# HshMain_v1_0.net
KiCad netlist of a schematic drawn in EAGLE
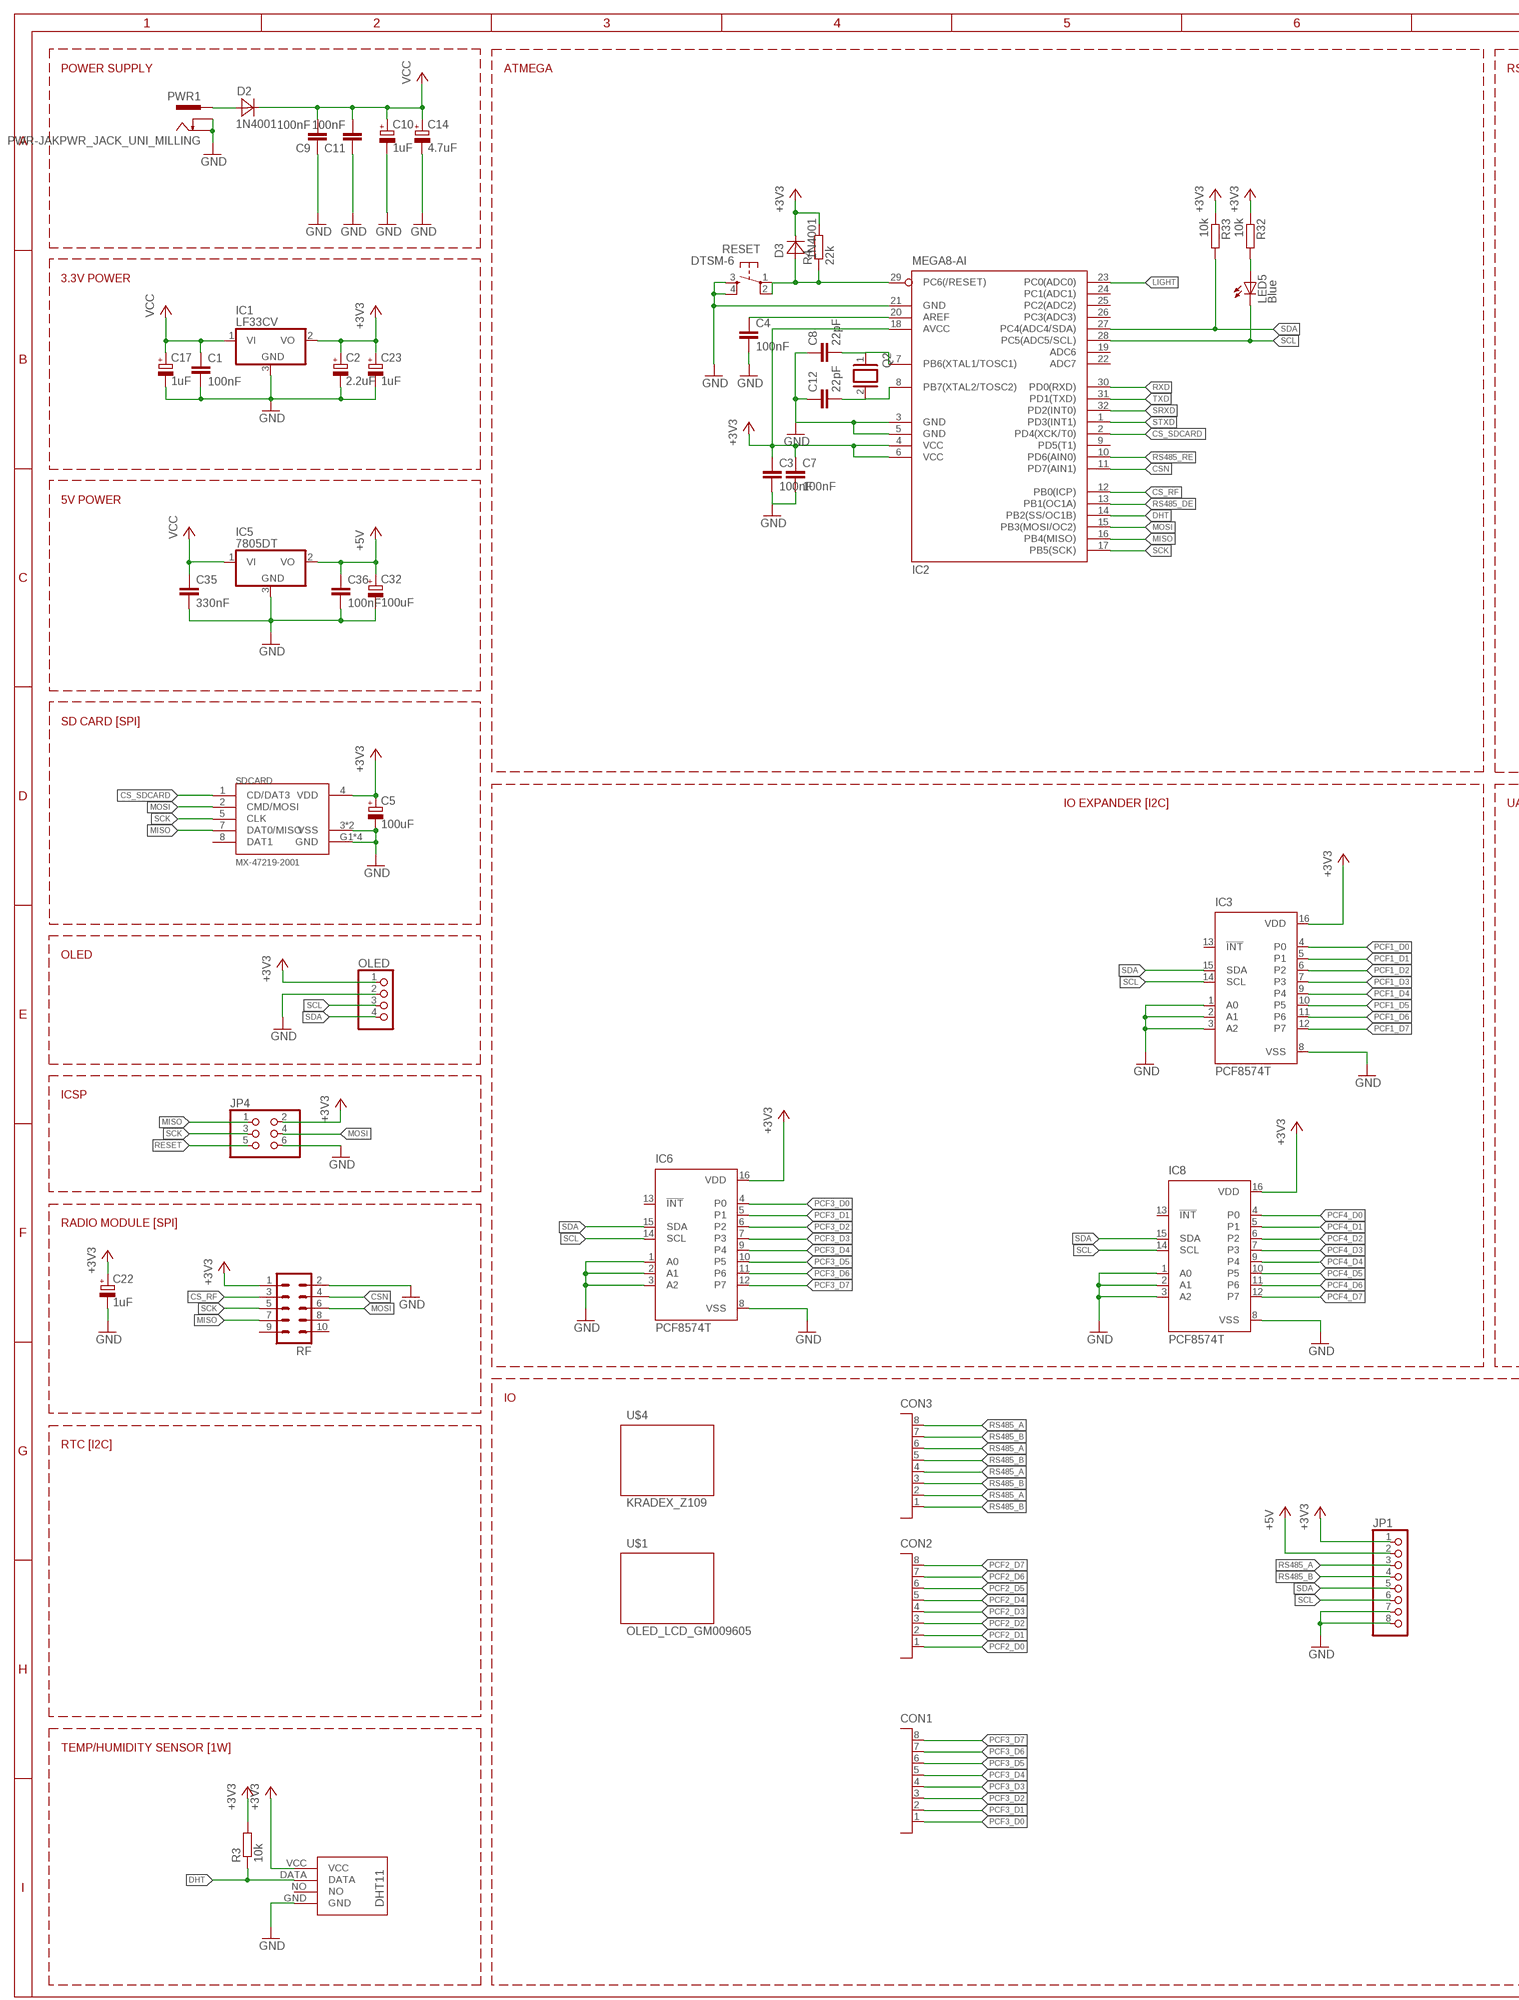
[diagram p0: schematic, sheet 1, part 1 of 2]
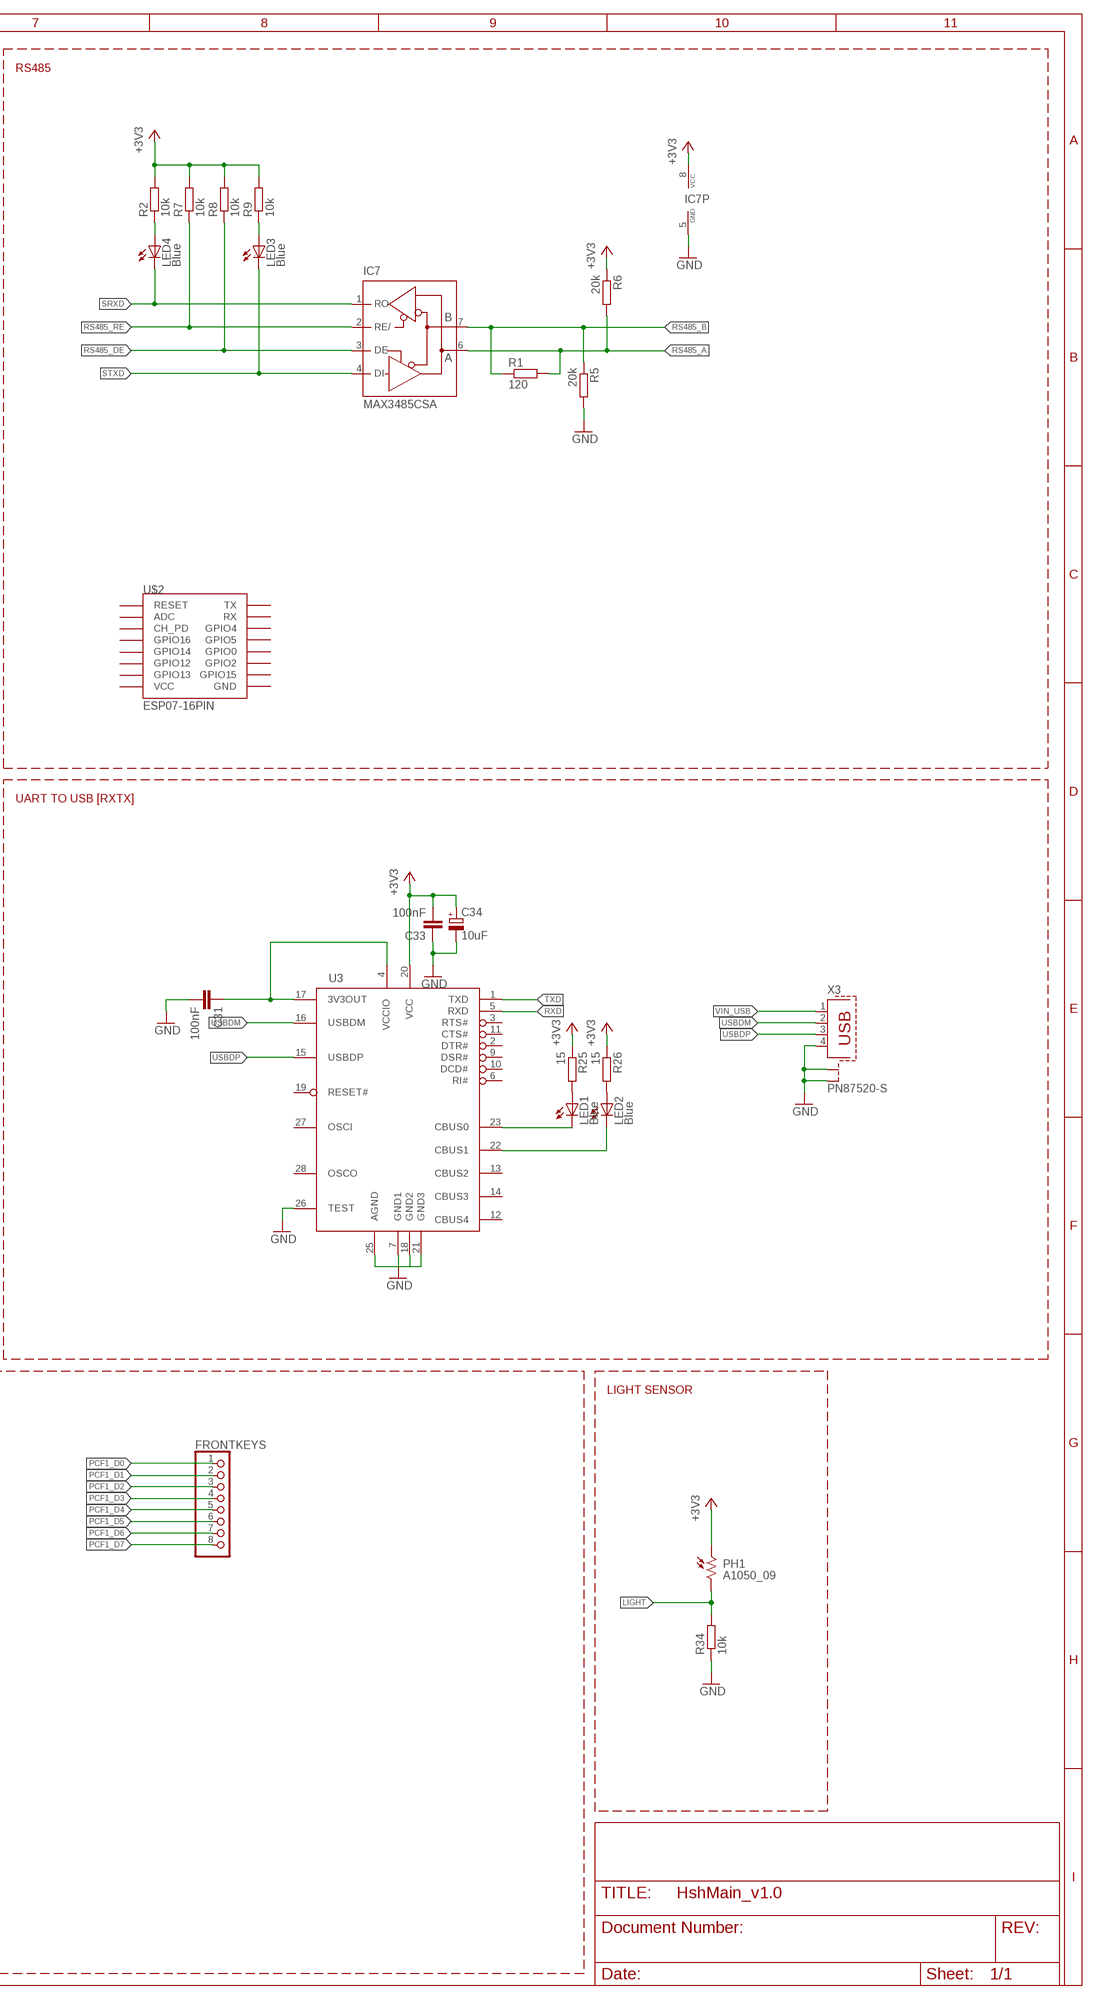
[diagram p1: schematic, sheet 1, part 2 of 2]

(export (version "E")
  (design (tool "Eeschema 10.0.6"))
  (components
    (comp (ref "C1")
      (value "100nF")
      (footprint "eagle-import:C0805")
      (libsource (lib "eagle-import") (part "C-EUC0805"))
    )
    (comp (ref "C2")
      (value "2.2uF")
      (footprint "eagle-import:PANASONIC_B")
      (libsource (lib "eagle-import") (part "CPOL-EUB"))
    )
    (comp (ref "C3")
      (value "100nF")
      (footprint "eagle-import:C0805")
      (libsource (lib "eagle-import") (part "C-EUC0805"))
    )
    (comp (ref "C4")
      (value "100nF")
      (footprint "eagle-import:C0805")
      (libsource (lib "eagle-import") (part "C-EUC0805"))
    )
    (comp (ref "C5")
      (value "100uF")
      (footprint "eagle-import:PANASONIC_D")
      (libsource (lib "eagle-import") (part "CPOL-EUD"))
    )
    (comp (ref "C7")
      (value "100nF")
      (footprint "eagle-import:C0805")
      (libsource (lib "eagle-import") (part "C-EUC0805"))
    )
    (comp (ref "C8")
      (value "22pF")
      (footprint "eagle-import:C0805")
      (libsource (lib "eagle-import") (part "C-EUC0805"))
    )
    (comp (ref "C9")
      (value "100nF")
      (footprint "eagle-import:C0805")
      (libsource (lib "eagle-import") (part "C-EUC0805"))
    )
    (comp (ref "C10")
      (value "1uF")
      (footprint "eagle-import:PANASONIC_B")
      (libsource (lib "eagle-import") (part "CPOL-EUB"))
    )
    (comp (ref "C11")
      (value "100nF")
      (footprint "eagle-import:C0805")
      (libsource (lib "eagle-import") (part "C-EUC0805"))
    )
    (comp (ref "C12")
      (value "22pF")
      (footprint "eagle-import:C0805")
      (libsource (lib "eagle-import") (part "C-EUC0805"))
    )
    (comp (ref "C14")
      (value "4.7uF")
      (footprint "eagle-import:PANASONIC_B")
      (libsource (lib "eagle-import") (part "CPOL-EUB"))
    )
    (comp (ref "C17")
      (value "1uF")
      (footprint "eagle-import:PANASONIC_B")
      (libsource (lib "eagle-import") (part "CPOL-EUB"))
    )
    (comp (ref "C22")
      (value "1uF")
      (footprint "eagle-import:PANASONIC_B")
      (libsource (lib "eagle-import") (part "CPOL-EUB"))
    )
    (comp (ref "C23")
      (value "1uF")
      (footprint "eagle-import:PANASONIC_B")
      (libsource (lib "eagle-import") (part "CPOL-EUB"))
    )
    (comp (ref "C31")
      (value "100nF")
      (footprint "eagle-import:C0805")
      (libsource (lib "eagle-import") (part "C-EUC0805"))
    )
    (comp (ref "C32")
      (value "100uF")
      (footprint "eagle-import:PANASONIC_D")
      (libsource (lib "eagle-import") (part "CPOL-EUD"))
    )
    (comp (ref "C33")
      (value "100nF")
      (footprint "eagle-import:C0805")
      (libsource (lib "eagle-import") (part "C-EUC0805"))
    )
    (comp (ref "C34")
      (value "10uF")
      (footprint "eagle-import:PANASONIC_B")
      (libsource (lib "eagle-import") (part "CPOL-EUB"))
    )
    (comp (ref "C35")
      (value "330nF")
      (footprint "eagle-import:C0805")
      (libsource (lib "eagle-import") (part "C-EUC0805"))
    )
    (comp (ref "C36")
      (value "100nF")
      (footprint "eagle-import:C0805")
      (libsource (lib "eagle-import") (part "C-EUC0805"))
    )
    (comp (ref "CON1")
      (value "15EDGRC-3.81-8P")
      (footprint "eagle-import:15EDGRC-3.81-8P")
      (libsource (lib "eagle-import") (part "15EDGRC-3.81-8P"))
    )
    (comp (ref "CON2")
      (value "15EDGRC-3.81-8P")
      (footprint "eagle-import:15EDGRC-3.81-8P")
      (libsource (lib "eagle-import") (part "15EDGRC-3.81-8P"))
    )
    (comp (ref "CON3")
      (value "15EDGRC-3.81-8P")
      (footprint "eagle-import:15EDGRC-3.81-8P")
      (libsource (lib "eagle-import") (part "15EDGRC-3.81-8P"))
    )
    (comp (ref "D2")
      (value "1N4001")
      (footprint "eagle-import:SMA")
      (libsource (lib "eagle-import") (part "MBRA340T3"))
    )
    (comp (ref "D3")
      (value "1N4001")
      (footprint "eagle-import:SMA")
      (libsource (lib "eagle-import") (part "MBRA340T3"))
    )
    (comp (ref "FRONTKEYS")
      (value "PINHD-1X8/90")
      (footprint "eagle-import:1X08_90")
      (libsource (lib "eagle-import") (part "PINHD-1X8/90"))
    )
    (comp (ref "IC1")
      (value "LF33CV")
      (footprint "eagle-import:TO252")
      (libsource (lib "eagle-import") (part "78DT"))
    )
    (comp (ref "IC2")
      (value "MEGA8-AI")
      (footprint "eagle-import:TQFP32-08")
      (fields (field (name "MPN") "ATMEGA8-16AU"))
      (libsource (lib "eagle-import") (part "MEGA8-AI"))
    )
    (comp (ref "IC3")
      (value "PCF8574T")
      (footprint "eagle-import:SO16W")
      (fields (field (name "MPN") "PCF8574T/3,512"))
      (libsource (lib "eagle-import") (part "PCF8574T"))
    )
    (comp (ref "IC5")
      (value "7805DT")
      (footprint "eagle-import:TO252")
      (libsource (lib "eagle-import") (part "linear_78DT05"))
    )
    (comp (ref "IC6")
      (value "PCF8574T")
      (footprint "eagle-import:SO16W")
      (fields (field (name "MPN") "PCF8574T/3,512"))
      (libsource (lib "eagle-import") (part "PCF8574T"))
    )
    (comp (ref "IC7")
      (value "MAX3485CSA")
      (footprint "eagle-import:SO08")
      (fields (field (name "MF") "MAXIM") (field (name "MPN") "MAX481CSA"))
      (libsource (lib "eagle-import") (part "MAX481CSA"))
    )
    (comp (ref "IC8")
      (value "PCF8574T")
      (footprint "eagle-import:SO16W")
      (fields (field (name "MPN") "PCF8574T/3,512"))
      (libsource (lib "eagle-import") (part "PCF8574T"))
    )
    (comp (ref "JP1")
      (value "PINHD-1X8/90")
      (footprint "eagle-import:1X08_90")
      (libsource (lib "eagle-import") (part "PINHD-1X8/90"))
    )
    (comp (ref "JP4")
      (value "PINHD-2X3")
      (footprint "eagle-import:2X03")
      (libsource (lib "eagle-import") (part "PINHD-2X3"))
    )
    (comp (ref "LED1")
      (value "Blue")
      (footprint "eagle-import:SML0805")
      (libsource (lib "eagle-import") (part "LEDSML0805"))
    )
    (comp (ref "LED2")
      (value "Blue")
      (footprint "eagle-import:SML0805")
      (libsource (lib "eagle-import") (part "LEDSML0805"))
    )
    (comp (ref "LED3")
      (value "Blue")
      (footprint "eagle-import:SML0805")
      (libsource (lib "eagle-import") (part "LEDSML0805"))
    )
    (comp (ref "LED4")
      (value "Blue")
      (footprint "eagle-import:SML0805")
      (libsource (lib "eagle-import") (part "LEDSML0805"))
    )
    (comp (ref "LED5")
      (value "Blue")
      (footprint "eagle-import:SML0805")
      (libsource (lib "eagle-import") (part "LEDSML0805"))
    )
    (comp (ref "OLED")
      (value "PINHD-1X4")
      (footprint "eagle-import:1X04")
      (libsource (lib "eagle-import") (part "PINHD-1X4"))
    )
    (comp (ref "PH1")
      (value "A1050_09")
      (footprint "eagle-import:T0-46-A10XX")
      (libsource (lib "eagle-import") (part "A1050_09"))
    )
    (comp (ref "PWR1")
      (value "PWR-JAKPWR_JACK_UNI_MILLING")
      (footprint "eagle-import:PWR_JACK_UNI_MILLING")
      (libsource (lib "eagle-import") (part "PWR-JAKPWR_JACK_UNI_MILLING"))
    )
    (comp (ref "Q2")
      (value "XTAL/S")
      (footprint "eagle-import:QS")
      (libsource (lib "eagle-import") (part "XTAL/S"))
    )
    (comp (ref "R1")
      (value "120")
      (footprint "eagle-import:R0805")
      (libsource (lib "eagle-import") (part "R-EU_R0805"))
    )
    (comp (ref "R2")
      (value "10k")
      (footprint "eagle-import:R0805")
      (libsource (lib "eagle-import") (part "R-EU_R0805"))
    )
    (comp (ref "R3")
      (value "10k")
      (footprint "eagle-import:R0805")
      (libsource (lib "eagle-import") (part "R-EU_R0805"))
    )
    (comp (ref "R4")
      (value "22k")
      (footprint "eagle-import:R0805")
      (libsource (lib "eagle-import") (part "R-EU_R0805"))
    )
    (comp (ref "R5")
      (value "20k")
      (footprint "eagle-import:R0805")
      (libsource (lib "eagle-import") (part "R-EU_R0805"))
    )
    (comp (ref "R6")
      (value "20k")
      (footprint "eagle-import:R0805")
      (libsource (lib "eagle-import") (part "R-EU_R0805"))
    )
    (comp (ref "R7")
      (value "10k")
      (footprint "eagle-import:R0805")
      (libsource (lib "eagle-import") (part "R-EU_R0805"))
    )
    (comp (ref "R8")
      (value "10k")
      (footprint "eagle-import:R0805")
      (libsource (lib "eagle-import") (part "R-EU_R0805"))
    )
    (comp (ref "R9")
      (value "10k")
      (footprint "eagle-import:R0805")
      (libsource (lib "eagle-import") (part "R-EU_R0805"))
    )
    (comp (ref "R25")
      (value "15")
      (footprint "eagle-import:R0805")
      (libsource (lib "eagle-import") (part "R-EU_R0805"))
    )
    (comp (ref "R26")
      (value "15")
      (footprint "eagle-import:R0805")
      (libsource (lib "eagle-import") (part "R-EU_R0805"))
    )
    (comp (ref "R32")
      (value "10k")
      (footprint "eagle-import:R0805")
      (libsource (lib "eagle-import") (part "R-EU_R0805"))
    )
    (comp (ref "R33")
      (value "10k")
      (footprint "eagle-import:R0805")
      (libsource (lib "eagle-import") (part "R-EU_R0805"))
    )
    (comp (ref "R34")
      (value "10k")
      (footprint "eagle-import:R0805")
      (libsource (lib "eagle-import") (part "R-EU_R0805"))
    )
    (comp (ref "RESET")
      (value "DTSM-6")
      (footprint "eagle-import:DTSM-6")
      (libsource (lib "eagle-import") (part "DTSM-6"))
    )
    (comp (ref "RF")
      (value "ML10")
      (footprint "eagle-import:ML10")
      (libsource (lib "eagle-import") (part "ML10"))
    )
    (comp (ref "SDCARD")
      (value "MX-47219-2001")
      (footprint "eagle-import:MX-47219-2001")
      (libsource (lib "eagle-import") (part "MX-47219-2001"))
    )
    (comp (ref "U$1")
      (value "OLED_LCD_GM009605")
      (footprint "eagle-import:OLED_LCD_GM009605")
      (libsource (lib "eagle-import") (part "OLED_LCD_GM009605"))
    )
    (comp (ref "U$2")
      (value "ESP07-16PIN")
      (footprint "eagle-import:ESP07-16PIN")
      (libsource (lib "eagle-import") (part "ESP07-16PIN"))
    )
    (comp (ref "U$3")
      (value "DHT11-PION.")
      (footprint "eagle-import:DHT11-PION.")
      (libsource (lib "eagle-import") (part "DHT11-PION."))
    )
    (comp (ref "U$4")
      (value "KRADEX_Z109")
      (footprint "eagle-import:KRADEX_Z109")
      (libsource (lib "eagle-import") (part "KRADEX_Z109"))
    )
    (comp (ref "U3")
      (value "FT232RL")
      (footprint "eagle-import:SSOP28DB")
      (libsource (lib "eagle-import") (part "FT232RL"))
    )
    (comp (ref "X3")
      (value "PN87520-S")
      (footprint "eagle-import:PN87520-S")
      (libsource (lib "eagle-import") (part "PN87520-S"))
    )
  )
  (nets
    (net (code "1") (name "+3V3") (class "Default")
      (node (ref "C2") (pin "+") (pinfunction "+_+") (pintype "passive"))
      (node (ref "C22") (pin "+") (pinfunction "+_+") (pintype "passive"))
      (node (ref "C23") (pin "+") (pinfunction "+_+") (pintype "passive"))
      (node (ref "C3") (pin "1") (pinfunction "1_1") (pintype "passive"))
      (node (ref "C33") (pin "2") (pinfunction "2_2") (pintype "passive"))
      (node (ref "C34") (pin "+") (pinfunction "+_+") (pintype "passive"))
      (node (ref "C5") (pin "+") (pinfunction "+_+") (pintype "passive"))
      (node (ref "C7") (pin "1") (pinfunction "1_1") (pintype "passive"))
      (node (ref "D3") (pin "C") (pinfunction "C_C") (pintype "passive"))
      (node (ref "IC1") (pin "2") (pinfunction "VO_2") (pintype "passive"))
      (node (ref "IC2") (pin "18") (pinfunction "AVCC_18") (pintype "power_in"))
      (node (ref "IC2") (pin "4") (pinfunction "VCC_4") (pintype "power_in"))
      (node (ref "IC2") (pin "6") (pinfunction "VCC_6") (pintype "power_in"))
      (node (ref "IC3") (pin "16") (pinfunction "VDD_16") (pintype "power_in"))
      (node (ref "IC6") (pin "16") (pinfunction "VDD_16") (pintype "power_in"))
      (node (ref "IC7") (pin "8") (pinfunction "VCC_8") (pintype "power_in"))
      (node (ref "IC8") (pin "16") (pinfunction "VDD_16") (pintype "power_in"))
      (node (ref "JP1") (pin "1") (pinfunction "1_1") (pintype "passive"))
      (node (ref "JP4") (pin "2") (pinfunction "2_2") (pintype "passive"))
      (node (ref "OLED") (pin "1") (pinfunction "1_1") (pintype "passive"))
      (node (ref "PH1") (pin "1") (pinfunction "1_1") (pintype "passive"))
      (node (ref "R2") (pin "2") (pinfunction "2_2") (pintype "passive"))
      (node (ref "R25") (pin "1") (pinfunction "1_1") (pintype "passive"))
      (node (ref "R26") (pin "1") (pinfunction "1_1") (pintype "passive"))
      (node (ref "R3") (pin "2") (pinfunction "2_2") (pintype "passive"))
      (node (ref "R32") (pin "1") (pinfunction "1_1") (pintype "passive"))
      (node (ref "R33") (pin "1") (pinfunction "1_1") (pintype "passive"))
      (node (ref "R4") (pin "2") (pinfunction "2_2") (pintype "passive"))
      (node (ref "R6") (pin "1") (pinfunction "1_1") (pintype "passive"))
      (node (ref "R7") (pin "2") (pinfunction "2_2") (pintype "passive"))
      (node (ref "R8") (pin "2") (pinfunction "2_2") (pintype "passive"))
      (node (ref "R9") (pin "2") (pinfunction "2_2") (pintype "passive"))
      (node (ref "RF") (pin "1") (pinfunction "1_1") (pintype "passive"))
      (node (ref "SDCARD") (pin "4") (pinfunction "VDD_4") (pintype "bidirectional"))
      (node (ref "U$3") (pin "VCC") (pinfunction "VCC_VCC") (pintype "bidirectional"))
      (node (ref "U3") (pin "20") (pinfunction "VCC_20") (pintype "power_in"))
    )
    (net (code "2") (name "+5V") (class "Default")
      (node (ref "C32") (pin "+") (pinfunction "+_+") (pintype "passive"))
      (node (ref "C36") (pin "1") (pinfunction "1_1") (pintype "passive"))
      (node (ref "IC5") (pin "2") (pinfunction "VO_2") (pintype "passive"))
      (node (ref "JP1") (pin "2") (pinfunction "2_2") (pintype "passive"))
    )
    (net (code "3") (name "CSN") (class "Default")
      (node (ref "IC2") (pin "11") (pinfunction "PD7(AIN1)_11") (pintype "bidirectional"))
      (node (ref "RF") (pin "4") (pinfunction "4_4") (pintype "passive"))
    )
    (net (code "4") (name "CS_RF") (class "Default")
      (node (ref "IC2") (pin "12") (pinfunction "PB0(ICP)_12") (pintype "bidirectional"))
      (node (ref "RF") (pin "3") (pinfunction "3_3") (pintype "passive"))
    )
    (net (code "5") (name "CS_SDCARD") (class "Default")
      (node (ref "IC2") (pin "2") (pinfunction "PD4(XCK/T0)_2") (pintype "bidirectional"))
      (node (ref "SDCARD") (pin "1") (pinfunction "CD/DAT3_1") (pintype "bidirectional"))
    )
    (net (code "6") (name "DHT") (class "Default")
      (node (ref "IC2") (pin "14") (pinfunction "PB2(SS/OC1B)_14") (pintype "bidirectional"))
      (node (ref "R3") (pin "1") (pinfunction "1_1") (pintype "passive"))
      (node (ref "U$3") (pin "DATA") (pinfunction "DATA_DATA") (pintype "bidirectional"))
    )
    (net (code "7") (name "GND") (class "Default")
      (node (ref "C1") (pin "2") (pinfunction "2_2") (pintype "passive"))
      (node (ref "C10") (pin "-") (pinfunction "-_-") (pintype "passive"))
      (node (ref "C11") (pin "1") (pinfunction "1_1") (pintype "passive"))
      (node (ref "C12") (pin "1") (pinfunction "1_1") (pintype "passive"))
      (node (ref "C14") (pin "-") (pinfunction "-_-") (pintype "passive"))
      (node (ref "C17") (pin "-") (pinfunction "-_-") (pintype "passive"))
      (node (ref "C2") (pin "-") (pinfunction "-_-") (pintype "passive"))
      (node (ref "C22") (pin "-") (pinfunction "-_-") (pintype "passive"))
      (node (ref "C23") (pin "-") (pinfunction "-_-") (pintype "passive"))
      (node (ref "C3") (pin "2") (pinfunction "2_2") (pintype "passive"))
      (node (ref "C31") (pin "2") (pinfunction "2_2") (pintype "passive"))
      (node (ref "C32") (pin "-") (pinfunction "-_-") (pintype "passive"))
      (node (ref "C33") (pin "1") (pinfunction "1_1") (pintype "passive"))
      (node (ref "C34") (pin "-") (pinfunction "-_-") (pintype "passive"))
      (node (ref "C35") (pin "2") (pinfunction "2_2") (pintype "passive"))
      (node (ref "C36") (pin "2") (pinfunction "2_2") (pintype "passive"))
      (node (ref "C4") (pin "2") (pinfunction "2_2") (pintype "passive"))
      (node (ref "C5") (pin "-") (pinfunction "-_-") (pintype "passive"))
      (node (ref "C7") (pin "2") (pinfunction "2_2") (pintype "passive"))
      (node (ref "C8") (pin "1") (pinfunction "1_1") (pintype "passive"))
      (node (ref "C9") (pin "1") (pinfunction "1_1") (pintype "passive"))
      (node (ref "IC1") (pin "3") (pinfunction "GND_3") (pintype "passive"))
      (node (ref "IC2") (pin "21") (pinfunction "GND_21") (pintype "power_in"))
      (node (ref "IC2") (pin "3") (pinfunction "GND_3") (pintype "power_in"))
      (node (ref "IC2") (pin "5") (pinfunction "GND_5") (pintype "power_in"))
      (node (ref "IC3") (pin "1") (pinfunction "A0_1") (pintype "input"))
      (node (ref "IC3") (pin "2") (pinfunction "A1_2") (pintype "input"))
      (node (ref "IC3") (pin "3") (pinfunction "A2_3") (pintype "input"))
      (node (ref "IC3") (pin "8") (pinfunction "VSS_8") (pintype "power_in"))
      (node (ref "IC5") (pin "3") (pinfunction "GND_3") (pintype "passive"))
      (node (ref "IC6") (pin "1") (pinfunction "A0_1") (pintype "input"))
      (node (ref "IC6") (pin "2") (pinfunction "A1_2") (pintype "input"))
      (node (ref "IC6") (pin "3") (pinfunction "A2_3") (pintype "input"))
      (node (ref "IC6") (pin "8") (pinfunction "VSS_8") (pintype "power_in"))
      (node (ref "IC7") (pin "5") (pinfunction "GND_5") (pintype "power_in"))
      (node (ref "IC8") (pin "1") (pinfunction "A0_1") (pintype "input"))
      (node (ref "IC8") (pin "2") (pinfunction "A1_2") (pintype "input"))
      (node (ref "IC8") (pin "3") (pinfunction "A2_3") (pintype "input"))
      (node (ref "IC8") (pin "8") (pinfunction "VSS_8") (pintype "power_in"))
      (node (ref "JP1") (pin "7") (pinfunction "7_7") (pintype "passive"))
      (node (ref "JP1") (pin "8") (pinfunction "8_8") (pintype "passive"))
      (node (ref "JP4") (pin "6") (pinfunction "6_6") (pintype "passive"))
      (node (ref "OLED") (pin "2") (pinfunction "2_2") (pintype "passive"))
      (node (ref "PWR1") (pin "-") (pinfunction "-_-") (pintype "passive"))
      (node (ref "PWR1") (pin "--") (pinfunction "--_--") (pintype "passive"))
      (node (ref "PWR1") (pin "--1") (pinfunction "--_--1") (pintype "passive"))
      (node (ref "PWR1") (pin "--2") (pinfunction "--_--2") (pintype "passive"))
      (node (ref "PWR1") (pin "--3") (pinfunction "--_--3") (pintype "passive"))
      (node (ref "PWR1") (pin "--4") (pinfunction "--_--4") (pintype "passive"))
      (node (ref "PWR1") (pin "--5") (pinfunction "--_--5") (pintype "passive"))
      (node (ref "PWR1") (pin "--6") (pinfunction "--_--6") (pintype "passive"))
      (node (ref "PWR1") (pin "--7") (pinfunction "--_--7") (pintype "passive"))
      (node (ref "PWR1") (pin "--8") (pinfunction "--_--8") (pintype "passive"))
      (node (ref "PWR1") (pin "-1") (pinfunction "-_-1") (pintype "passive"))
      (node (ref "PWR1") (pin "-2") (pinfunction "-_-2") (pintype "passive"))
      (node (ref "PWR1") (pin "-3") (pinfunction "-_-3") (pintype "passive"))
      (node (ref "PWR1") (pin "-4") (pinfunction "-_-4") (pintype "passive"))
      (node (ref "PWR1") (pin "-5") (pinfunction "-_-5") (pintype "passive"))
      (node (ref "PWR1") (pin "-6") (pinfunction "-_-6") (pintype "passive"))
      (node (ref "PWR1") (pin "-7") (pinfunction "-_-7") (pintype "passive"))
      (node (ref "PWR1") (pin "-8") (pinfunction "-_-8") (pintype "passive"))
      (node (ref "R34") (pin "1") (pinfunction "1_1") (pintype "passive"))
      (node (ref "R5") (pin "2") (pinfunction "2_2") (pintype "passive"))
      (node (ref "RESET") (pin "3") (pinfunction "3_3") (pintype "passive"))
      (node (ref "RESET") (pin "4") (pinfunction "4_4") (pintype "passive"))
      (node (ref "RF") (pin "2") (pinfunction "2_2") (pintype "passive"))
      (node (ref "SDCARD") (pin "3") (pinfunction "VSS_3") (pintype "bidirectional"))
      (node (ref "SDCARD") (pin "6") (pinfunction "VSS_6") (pintype "bidirectional"))
      (node (ref "SDCARD") (pin "G1") (pinfunction "GND_G1") (pintype "bidirectional"))
      (node (ref "SDCARD") (pin "G2") (pinfunction "GND_G2") (pintype "bidirectional"))
      (node (ref "SDCARD") (pin "G3") (pinfunction "GND_G3") (pintype "bidirectional"))
      (node (ref "SDCARD") (pin "G4") (pinfunction "GND_G4") (pintype "bidirectional"))
      (node (ref "U$3") (pin "GND") (pinfunction "GND_GND") (pintype "bidirectional"))
      (node (ref "U3") (pin "18") (pinfunction "GND2_18") (pintype "power_in"))
      (node (ref "U3") (pin "21") (pinfunction "GND3_21") (pintype "power_in"))
      (node (ref "U3") (pin "25") (pinfunction "AGND_25") (pintype "power_in"))
      (node (ref "U3") (pin "26") (pinfunction "TEST_26") (pintype "input"))
      (node (ref "U3") (pin "7") (pinfunction "GND1_7") (pintype "power_in"))
      (node (ref "X3") (pin "4") (pinfunction "4_4") (pintype "passive"))
      (node (ref "X3") (pin "S1") (pinfunction "S1_S1") (pintype "passive"))
      (node (ref "X3") (pin "S2") (pinfunction "S2_S2") (pintype "passive"))
    )
    (net (code "8") (name "LIGHT") (class "Default")
      (node (ref "IC2") (pin "23") (pinfunction "PC0(ADC0)_23") (pintype "bidirectional"))
      (node (ref "PH1") (pin "2") (pinfunction "2_2") (pintype "passive"))
      (node (ref "R34") (pin "2") (pinfunction "2_2") (pintype "passive"))
    )
    (net (code "9") (name "MISO") (class "Default")
      (node (ref "IC2") (pin "16") (pinfunction "PB4(MISO)_16") (pintype "bidirectional"))
      (node (ref "JP4") (pin "1") (pinfunction "1_1") (pintype "passive"))
      (node (ref "RF") (pin "7") (pinfunction "7_7") (pintype "passive"))
      (node (ref "SDCARD") (pin "7") (pinfunction "DAT0/MISO_7") (pintype "bidirectional"))
    )
    (net (code "10") (name "MOSI") (class "Default")
      (node (ref "IC2") (pin "15") (pinfunction "PB3(MOSI/OC2)_15") (pintype "bidirectional"))
      (node (ref "JP4") (pin "4") (pinfunction "4_4") (pintype "passive"))
      (node (ref "RF") (pin "6") (pinfunction "6_6") (pintype "passive"))
      (node (ref "SDCARD") (pin "2") (pinfunction "CMD/MOSI_2") (pintype "bidirectional"))
    )
    (net (code "11") (name "Net-(D2-PadA)") (class "Default")
      (node (ref "D2") (pin "A") (pinfunction "A_A") (pintype "passive"))
      (node (ref "PWR1") (pin "+") (pinfunction "+_+") (pintype "passive"))
      (node (ref "PWR1") (pin "+1") (pinfunction "+_+1") (pintype "passive"))
      (node (ref "PWR1") (pin "+2") (pinfunction "+_+2") (pintype "passive"))
      (node (ref "PWR1") (pin "+3") (pinfunction "+_+3") (pintype "passive"))
      (node (ref "PWR1") (pin "+4") (pinfunction "+_+4") (pintype "passive"))
      (node (ref "PWR1") (pin "+5") (pinfunction "+_+5") (pintype "passive"))
      (node (ref "PWR1") (pin "+6") (pinfunction "+_+6") (pintype "passive"))
      (node (ref "PWR1") (pin "+7") (pinfunction "+_+7") (pintype "passive"))
      (node (ref "PWR1") (pin "+8") (pinfunction "+_+8") (pintype "passive"))
    )
    (net (code "12") (name "Net-(IC2-AREF)") (class "Default")
      (node (ref "C4") (pin "1") (pinfunction "1_1") (pintype "passive"))
      (node (ref "IC2") (pin "20") (pinfunction "AREF_20") (pintype "passive"))
    )
    (net (code "13") (name "Net-(IC2-PB6(XTAL1{slash}TOSC1))") (class "Default")
      (node (ref "C8") (pin "2") (pinfunction "2_2") (pintype "passive"))
      (node (ref "IC2") (pin "7") (pinfunction "PB6(XTAL1/TOSC1)_7") (pintype "bidirectional"))
      (node (ref "Q2") (pin "1") (pinfunction "1_1") (pintype "passive"))
    )
    (net (code "14") (name "Net-(IC2-PB7(XTAL2{slash}TOSC2))") (class "Default")
      (node (ref "C12") (pin "2") (pinfunction "2_2") (pintype "passive"))
      (node (ref "IC2") (pin "8") (pinfunction "PB7(XTAL2/TOSC2)_8") (pintype "bidirectional"))
      (node (ref "Q2") (pin "2") (pinfunction "2_2") (pintype "passive"))
    )
    (net (code "15") (name "Net-(LED1-PadA)") (class "Default")
      (node (ref "LED1") (pin "A") (pinfunction "A_A") (pintype "passive"))
      (node (ref "R25") (pin "2") (pinfunction "2_2") (pintype "passive"))
    )
    (net (code "16") (name "Net-(LED2-PadA)") (class "Default")
      (node (ref "LED2") (pin "A") (pinfunction "A_A") (pintype "passive"))
      (node (ref "R26") (pin "2") (pinfunction "2_2") (pintype "passive"))
    )
    (net (code "17") (name "Net-(LED3-PadA)") (class "Default")
      (node (ref "LED3") (pin "A") (pinfunction "A_A") (pintype "passive"))
      (node (ref "R9") (pin "1") (pinfunction "1_1") (pintype "passive"))
    )
    (net (code "18") (name "Net-(LED4-PadA)") (class "Default")
      (node (ref "LED4") (pin "A") (pinfunction "A_A") (pintype "passive"))
      (node (ref "R2") (pin "1") (pinfunction "1_1") (pintype "passive"))
    )
    (net (code "19") (name "Net-(LED5-PadA)") (class "Default")
      (node (ref "LED5") (pin "A") (pinfunction "A_A") (pintype "passive"))
      (node (ref "R32") (pin "2") (pinfunction "2_2") (pintype "passive"))
    )
    (net (code "20") (name "Net-(U3-3V3OUT)") (class "Default")
      (node (ref "C31") (pin "1") (pinfunction "1_1") (pintype "passive"))
      (node (ref "U3") (pin "17") (pinfunction "3V3OUT_17") (pintype "output"))
      (node (ref "U3") (pin "4") (pinfunction "VCCIO_4") (pintype "power_in"))
    )
    (net (code "21") (name "Net-(U3-CBUS0)") (class "Default")
      (node (ref "LED1") (pin "C") (pinfunction "C_C") (pintype "passive"))
      (node (ref "U3") (pin "23") (pinfunction "CBUS0_23") (pintype "bidirectional"))
    )
    (net (code "22") (name "Net-(U3-CBUS1)") (class "Default")
      (node (ref "LED2") (pin "C") (pinfunction "C_C") (pintype "passive"))
      (node (ref "U3") (pin "22") (pinfunction "CBUS1_22") (pintype "bidirectional"))
    )
    (net (code "23") (name "PCF1_D0") (class "Default")
      (node (ref "FRONTKEYS") (pin "1") (pinfunction "1_1") (pintype "passive"))
      (node (ref "IC3") (pin "4") (pinfunction "P0_4") (pintype "bidirectional"))
    )
    (net (code "24") (name "PCF1_D1") (class "Default")
      (node (ref "FRONTKEYS") (pin "2") (pinfunction "2_2") (pintype "passive"))
      (node (ref "IC3") (pin "5") (pinfunction "P1_5") (pintype "bidirectional"))
    )
    (net (code "25") (name "PCF1_D2") (class "Default")
      (node (ref "FRONTKEYS") (pin "3") (pinfunction "3_3") (pintype "passive"))
      (node (ref "IC3") (pin "6") (pinfunction "P2_6") (pintype "bidirectional"))
    )
    (net (code "26") (name "PCF1_D3") (class "Default")
      (node (ref "FRONTKEYS") (pin "4") (pinfunction "4_4") (pintype "passive"))
      (node (ref "IC3") (pin "7") (pinfunction "P3_7") (pintype "bidirectional"))
    )
    (net (code "27") (name "PCF1_D4") (class "Default")
      (node (ref "FRONTKEYS") (pin "5") (pinfunction "5_5") (pintype "passive"))
      (node (ref "IC3") (pin "9") (pinfunction "P4_9") (pintype "bidirectional"))
    )
    (net (code "28") (name "PCF1_D5") (class "Default")
      (node (ref "FRONTKEYS") (pin "6") (pinfunction "6_6") (pintype "passive"))
      (node (ref "IC3") (pin "10") (pinfunction "P5_10") (pintype "bidirectional"))
    )
    (net (code "29") (name "PCF1_D6") (class "Default")
      (node (ref "FRONTKEYS") (pin "7") (pinfunction "7_7") (pintype "passive"))
      (node (ref "IC3") (pin "11") (pinfunction "P6_11") (pintype "bidirectional"))
    )
    (net (code "30") (name "PCF1_D7") (class "Default")
      (node (ref "FRONTKEYS") (pin "8") (pinfunction "8_8") (pintype "passive"))
      (node (ref "IC3") (pin "12") (pinfunction "P7_12") (pintype "bidirectional"))
    )
    (net (code "31") (name "PCF2_D0") (class "Default")
      (node (ref "CON2") (pin "1") (pinfunction "P$1_1") (pintype "bidirectional"))
    )
    (net (code "32") (name "PCF2_D1") (class "Default")
      (node (ref "CON2") (pin "2") (pinfunction "P$2_2") (pintype "bidirectional"))
    )
    (net (code "33") (name "PCF2_D2") (class "Default")
      (node (ref "CON2") (pin "3") (pinfunction "P$3_3") (pintype "bidirectional"))
    )
    (net (code "34") (name "PCF2_D3") (class "Default")
      (node (ref "CON2") (pin "4") (pinfunction "P$4_4") (pintype "bidirectional"))
    )
    (net (code "35") (name "PCF2_D4") (class "Default")
      (node (ref "CON2") (pin "5") (pinfunction "P$5_5") (pintype "bidirectional"))
    )
    (net (code "36") (name "PCF2_D5") (class "Default")
      (node (ref "CON2") (pin "6") (pinfunction "P$6_6") (pintype "bidirectional"))
    )
    (net (code "37") (name "PCF2_D6") (class "Default")
      (node (ref "CON2") (pin "7") (pinfunction "P$7_7") (pintype "bidirectional"))
    )
    (net (code "38") (name "PCF2_D7") (class "Default")
      (node (ref "CON2") (pin "8") (pinfunction "P$8_8") (pintype "bidirectional"))
    )
    (net (code "39") (name "PCF3_D0") (class "Default")
      (node (ref "CON1") (pin "1") (pinfunction "P$1_1") (pintype "bidirectional"))
      (node (ref "IC6") (pin "4") (pinfunction "P0_4") (pintype "bidirectional"))
    )
    (net (code "40") (name "PCF3_D1") (class "Default")
      (node (ref "CON1") (pin "2") (pinfunction "P$2_2") (pintype "bidirectional"))
      (node (ref "IC6") (pin "5") (pinfunction "P1_5") (pintype "bidirectional"))
    )
    (net (code "41") (name "PCF3_D2") (class "Default")
      (node (ref "CON1") (pin "3") (pinfunction "P$3_3") (pintype "bidirectional"))
      (node (ref "IC6") (pin "6") (pinfunction "P2_6") (pintype "bidirectional"))
    )
    (net (code "42") (name "PCF3_D3") (class "Default")
      (node (ref "CON1") (pin "4") (pinfunction "P$4_4") (pintype "bidirectional"))
      (node (ref "IC6") (pin "7") (pinfunction "P3_7") (pintype "bidirectional"))
    )
    (net (code "43") (name "PCF3_D4") (class "Default")
      (node (ref "CON1") (pin "5") (pinfunction "P$5_5") (pintype "bidirectional"))
      (node (ref "IC6") (pin "9") (pinfunction "P4_9") (pintype "bidirectional"))
    )
    (net (code "44") (name "PCF3_D5") (class "Default")
      (node (ref "CON1") (pin "6") (pinfunction "P$6_6") (pintype "bidirectional"))
      (node (ref "IC6") (pin "10") (pinfunction "P5_10") (pintype "bidirectional"))
    )
    (net (code "45") (name "PCF3_D6") (class "Default")
      (node (ref "CON1") (pin "7") (pinfunction "P$7_7") (pintype "bidirectional"))
      (node (ref "IC6") (pin "11") (pinfunction "P6_11") (pintype "bidirectional"))
    )
    (net (code "46") (name "PCF3_D7") (class "Default")
      (node (ref "CON1") (pin "8") (pinfunction "P$8_8") (pintype "bidirectional"))
      (node (ref "IC6") (pin "12") (pinfunction "P7_12") (pintype "bidirectional"))
    )
    (net (code "47") (name "PCF4_D0") (class "Default")
      (node (ref "IC8") (pin "4") (pinfunction "P0_4") (pintype "bidirectional"))
    )
    (net (code "48") (name "PCF4_D1") (class "Default")
      (node (ref "IC8") (pin "5") (pinfunction "P1_5") (pintype "bidirectional"))
    )
    (net (code "49") (name "PCF4_D2") (class "Default")
      (node (ref "IC8") (pin "6") (pinfunction "P2_6") (pintype "bidirectional"))
    )
    (net (code "50") (name "PCF4_D3") (class "Default")
      (node (ref "IC8") (pin "7") (pinfunction "P3_7") (pintype "bidirectional"))
    )
    (net (code "51") (name "PCF4_D4") (class "Default")
      (node (ref "IC8") (pin "9") (pinfunction "P4_9") (pintype "bidirectional"))
    )
    (net (code "52") (name "PCF4_D5") (class "Default")
      (node (ref "IC8") (pin "10") (pinfunction "P5_10") (pintype "bidirectional"))
    )
    (net (code "53") (name "PCF4_D6") (class "Default")
      (node (ref "IC8") (pin "11") (pinfunction "P6_11") (pintype "bidirectional"))
    )
    (net (code "54") (name "PCF4_D7") (class "Default")
      (node (ref "IC8") (pin "12") (pinfunction "P7_12") (pintype "bidirectional"))
    )
    (net (code "55") (name "RESET") (class "Default")
      (node (ref "D3") (pin "A") (pinfunction "A_A") (pintype "passive"))
      (node (ref "IC2") (pin "29") (pinfunction "PC6(/RESET)_29") (pintype "bidirectional"))
      (node (ref "JP4") (pin "5") (pinfunction "5_5") (pintype "passive"))
      (node (ref "R4") (pin "1") (pinfunction "1_1") (pintype "passive"))
      (node (ref "RESET") (pin "1") (pinfunction "1_1") (pintype "passive"))
      (node (ref "RESET") (pin "2") (pinfunction "2_2") (pintype "passive"))
    )
    (net (code "56") (name "RS485_A") (class "Default")
      (node (ref "CON3") (pin "2") (pinfunction "P$2_2") (pintype "bidirectional"))
      (node (ref "CON3") (pin "4") (pinfunction "P$4_4") (pintype "bidirectional"))
      (node (ref "CON3") (pin "6") (pinfunction "P$6_6") (pintype "bidirectional"))
      (node (ref "CON3") (pin "8") (pinfunction "P$8_8") (pintype "bidirectional"))
      (node (ref "IC7") (pin "6") (pinfunction "A_6") (pintype "passive"))
      (node (ref "JP1") (pin "3") (pinfunction "3_3") (pintype "passive"))
      (node (ref "R1") (pin "2") (pinfunction "2_2") (pintype "passive"))
      (node (ref "R6") (pin "2") (pinfunction "2_2") (pintype "passive"))
    )
    (net (code "57") (name "RS485_B") (class "Default")
      (node (ref "CON3") (pin "1") (pinfunction "P$1_1") (pintype "bidirectional"))
      (node (ref "CON3") (pin "3") (pinfunction "P$3_3") (pintype "bidirectional"))
      (node (ref "CON3") (pin "5") (pinfunction "P$5_5") (pintype "bidirectional"))
      (node (ref "CON3") (pin "7") (pinfunction "P$7_7") (pintype "bidirectional"))
      (node (ref "IC7") (pin "7") (pinfunction "B_7") (pintype "passive"))
      (node (ref "JP1") (pin "4") (pinfunction "4_4") (pintype "passive"))
      (node (ref "R1") (pin "1") (pinfunction "1_1") (pintype "passive"))
      (node (ref "R5") (pin "1") (pinfunction "1_1") (pintype "passive"))
    )
    (net (code "58") (name "RS485_DE") (class "Default")
      (node (ref "IC2") (pin "13") (pinfunction "PB1(OC1A)_13") (pintype "bidirectional"))
      (node (ref "IC7") (pin "3") (pinfunction "DE_3") (pintype "input"))
      (node (ref "R8") (pin "1") (pinfunction "1_1") (pintype "passive"))
    )
    (net (code "59") (name "RS485_RE") (class "Default")
      (node (ref "IC2") (pin "10") (pinfunction "PD6(AIN0)_10") (pintype "bidirectional"))
      (node (ref "IC7") (pin "2") (pinfunction "RE/_2") (pintype "input"))
      (node (ref "R7") (pin "1") (pinfunction "1_1") (pintype "passive"))
    )
    (net (code "60") (name "RXD") (class "Default")
      (node (ref "IC2") (pin "30") (pinfunction "PD0(RXD)_30") (pintype "bidirectional"))
      (node (ref "U3") (pin "5") (pinfunction "RXD_5") (pintype "input"))
    )
    (net (code "61") (name "SCK") (class "Default")
      (node (ref "IC2") (pin "17") (pinfunction "PB5(SCK)_17") (pintype "bidirectional"))
      (node (ref "JP4") (pin "3") (pinfunction "3_3") (pintype "passive"))
      (node (ref "RF") (pin "5") (pinfunction "5_5") (pintype "passive"))
      (node (ref "SDCARD") (pin "5") (pinfunction "CLK_5") (pintype "bidirectional"))
    )
    (net (code "62") (name "SCL") (class "Default")
      (node (ref "IC2") (pin "28") (pinfunction "PC5(ADC5/SCL)_28") (pintype "bidirectional"))
      (node (ref "IC3") (pin "14") (pinfunction "SCL_14") (pintype "input"))
      (node (ref "IC6") (pin "14") (pinfunction "SCL_14") (pintype "input"))
      (node (ref "IC8") (pin "14") (pinfunction "SCL_14") (pintype "input"))
      (node (ref "JP1") (pin "6") (pinfunction "6_6") (pintype "passive"))
      (node (ref "LED5") (pin "C") (pinfunction "C_C") (pintype "passive"))
      (node (ref "OLED") (pin "3") (pinfunction "3_3") (pintype "passive"))
    )
    (net (code "63") (name "SDA") (class "Default")
      (node (ref "IC2") (pin "27") (pinfunction "PC4(ADC4/SDA)_27") (pintype "bidirectional"))
      (node (ref "IC3") (pin "15") (pinfunction "SDA_15") (pintype "bidirectional"))
      (node (ref "IC6") (pin "15") (pinfunction "SDA_15") (pintype "bidirectional"))
      (node (ref "IC8") (pin "15") (pinfunction "SDA_15") (pintype "bidirectional"))
      (node (ref "JP1") (pin "5") (pinfunction "5_5") (pintype "passive"))
      (node (ref "OLED") (pin "4") (pinfunction "4_4") (pintype "passive"))
      (node (ref "R33") (pin "2") (pinfunction "2_2") (pintype "passive"))
    )
    (net (code "64") (name "SRXD") (class "Default")
      (node (ref "IC2") (pin "32") (pinfunction "PD2(INT0)_32") (pintype "bidirectional"))
      (node (ref "IC7") (pin "1") (pinfunction "RO_1") (pintype "output"))
      (node (ref "LED4") (pin "C") (pinfunction "C_C") (pintype "passive"))
    )
    (net (code "65") (name "STXD") (class "Default")
      (node (ref "IC2") (pin "1") (pinfunction "PD3(INT1)_1") (pintype "bidirectional"))
      (node (ref "IC7") (pin "4") (pinfunction "DI_4") (pintype "input"))
      (node (ref "LED3") (pin "C") (pinfunction "C_C") (pintype "passive"))
    )
    (net (code "66") (name "TXD") (class "Default")
      (node (ref "IC2") (pin "31") (pinfunction "PD1(TXD)_31") (pintype "bidirectional"))
      (node (ref "U3") (pin "1") (pinfunction "TXD_1") (pintype "output"))
    )
    (net (code "67") (name "USBDM") (class "Default")
      (node (ref "U3") (pin "16") (pinfunction "USBDM_16") (pintype "bidirectional"))
      (node (ref "X3") (pin "2") (pinfunction "2_2") (pintype "passive"))
    )
    (net (code "68") (name "USBDP") (class "Default")
      (node (ref "U3") (pin "15") (pinfunction "USBDP_15") (pintype "bidirectional"))
      (node (ref "X3") (pin "3") (pinfunction "3_3") (pintype "passive"))
    )
    (net (code "69") (name "VCC") (class "Default")
      (node (ref "C1") (pin "1") (pinfunction "1_1") (pintype "passive"))
      (node (ref "C10") (pin "+") (pinfunction "+_+") (pintype "passive"))
      (node (ref "C11") (pin "2") (pinfunction "2_2") (pintype "passive"))
      (node (ref "C14") (pin "+") (pinfunction "+_+") (pintype "passive"))
      (node (ref "C17") (pin "+") (pinfunction "+_+") (pintype "passive"))
      (node (ref "C35") (pin "1") (pinfunction "1_1") (pintype "passive"))
      (node (ref "C9") (pin "2") (pinfunction "2_2") (pintype "passive"))
      (node (ref "D2") (pin "C") (pinfunction "C_C") (pintype "passive"))
      (node (ref "IC1") (pin "1") (pinfunction "VI_1") (pintype "input"))
      (node (ref "IC5") (pin "1") (pinfunction "VI_1") (pintype "input"))
    )
    (net (code "70") (name "VIN_USB") (class "Default")
      (node (ref "X3") (pin "1") (pinfunction "1_1") (pintype "passive"))
    )
    (net (code "71") (name "unconnected-(IC2-ADC6-Pad19)") (class "Default")
      (node (ref "IC2") (pin "19") (pinfunction "ADC6_19") (pintype "bidirectional"))
    )
    (net (code "72") (name "unconnected-(IC2-ADC7-Pad22)") (class "Default")
      (node (ref "IC2") (pin "22") (pinfunction "ADC7_22") (pintype "bidirectional"))
    )
    (net (code "73") (name "unconnected-(IC2-PC1(ADC1)-Pad24)") (class "Default")
      (node (ref "IC2") (pin "24") (pinfunction "PC1(ADC1)_24") (pintype "bidirectional"))
    )
    (net (code "74") (name "unconnected-(IC2-PC2(ADC2)-Pad25)") (class "Default")
      (node (ref "IC2") (pin "25") (pinfunction "PC2(ADC2)_25") (pintype "bidirectional"))
    )
    (net (code "75") (name "unconnected-(IC2-PC3(ADC3)-Pad26)") (class "Default")
      (node (ref "IC2") (pin "26") (pinfunction "PC3(ADC3)_26") (pintype "bidirectional"))
    )
    (net (code "76") (name "unconnected-(IC2-PD5(T1)-Pad9)") (class "Default")
      (node (ref "IC2") (pin "9") (pinfunction "PD5(T1)_9") (pintype "bidirectional"))
    )
    (net (code "77") (name "unconnected-(IC3-~{INT}-Pad13)") (class "Default")
      (node (ref "IC3") (pin "13") (pinfunction "~{INT}_13") (pintype "output"))
    )
    (net (code "78") (name "unconnected-(IC6-~{INT}-Pad13)") (class "Default")
      (node (ref "IC6") (pin "13") (pinfunction "~{INT}_13") (pintype "output"))
    )
    (net (code "79") (name "unconnected-(IC8-~{INT}-Pad13)") (class "Default")
      (node (ref "IC8") (pin "13") (pinfunction "~{INT}_13") (pintype "output"))
    )
    (net (code "80") (name "unconnected-(RF-Pad8)") (class "Default")
      (node (ref "RF") (pin "8") (pinfunction "8_8") (pintype "passive"))
    )
    (net (code "81") (name "unconnected-(RF-Pad9)") (class "Default")
      (node (ref "RF") (pin "9") (pinfunction "9_9") (pintype "passive"))
    )
    (net (code "82") (name "unconnected-(RF-Pad10)") (class "Default")
      (node (ref "RF") (pin "10") (pinfunction "10_10") (pintype "passive"))
    )
    (net (code "83") (name "unconnected-(SDCARD-DAT1-Pad8)") (class "Default")
      (node (ref "SDCARD") (pin "8") (pinfunction "DAT1_8") (pintype "bidirectional"))
    )
    (net (code "84") (name "unconnected-(U$2-PadADC)") (class "Default")
      (node (ref "U$2") (pin "ADC") (pinfunction "ADC_ADC") (pintype "bidirectional"))
    )
    (net (code "85") (name "unconnected-(U$2-PadCH_PD)") (class "Default")
      (node (ref "U$2") (pin "CH_PD") (pinfunction "CH_PD_CH_PD") (pintype "bidirectional"))
    )
    (net (code "86") (name "unconnected-(U$2-PadGND)") (class "Default")
      (node (ref "U$2") (pin "GND") (pinfunction "GND_GND") (pintype "bidirectional"))
    )
    (net (code "87") (name "unconnected-(U$2-PadGPIO0)") (class "Default")
      (node (ref "U$2") (pin "GPIO0") (pinfunction "GPIO0_GPIO0") (pintype "bidirectional"))
    )
    (net (code "88") (name "unconnected-(U$2-PadGPIO2)") (class "Default")
      (node (ref "U$2") (pin "GPIO2") (pinfunction "GPIO2_GPIO2") (pintype "bidirectional"))
    )
    (net (code "89") (name "unconnected-(U$2-PadGPIO4)") (class "Default")
      (node (ref "U$2") (pin "GPIO4") (pinfunction "GPIO4_GPIO4") (pintype "bidirectional"))
    )
    (net (code "90") (name "unconnected-(U$2-PadGPIO5)") (class "Default")
      (node (ref "U$2") (pin "GPIO5") (pinfunction "GPIO5_GPIO5") (pintype "bidirectional"))
    )
    (net (code "91") (name "unconnected-(U$2-PadGPIO12)") (class "Default")
      (node (ref "U$2") (pin "GPIO12") (pinfunction "GPIO12_GPIO12") (pintype "bidirectional"))
    )
    (net (code "92") (name "unconnected-(U$2-PadGPIO13)") (class "Default")
      (node (ref "U$2") (pin "GPIO13") (pinfunction "GPIO13_GPIO13") (pintype "bidirectional"))
    )
    (net (code "93") (name "unconnected-(U$2-PadGPIO14)") (class "Default")
      (node (ref "U$2") (pin "GPIO14") (pinfunction "GPIO14_GPIO14") (pintype "bidirectional"))
    )
    (net (code "94") (name "unconnected-(U$2-PadGPIO15)") (class "Default")
      (node (ref "U$2") (pin "GPIO15") (pinfunction "GPIO15_GPIO15") (pintype "bidirectional"))
    )
    (net (code "95") (name "unconnected-(U$2-PadGPIO16)") (class "Default")
      (node (ref "U$2") (pin "GPIO16") (pinfunction "GPIO16_GPIO16") (pintype "bidirectional"))
    )
    (net (code "96") (name "unconnected-(U$2-PadRX)") (class "Default")
      (node (ref "U$2") (pin "RX") (pinfunction "RX_RX") (pintype "bidirectional"))
    )
    (net (code "97") (name "unconnected-(U$2-PadTX)") (class "Default")
      (node (ref "U$2") (pin "TX") (pinfunction "TX_TX") (pintype "bidirectional"))
    )
    (net (code "98") (name "unconnected-(U$2-PadVCC)") (class "Default")
      (node (ref "U$2") (pin "VCC") (pinfunction "VCC_VCC") (pintype "bidirectional"))
    )
    (net (code "99") (name "unconnected-(U$2-RESET-PadREST)") (class "Default")
      (node (ref "U$2") (pin "REST") (pinfunction "RESET_REST") (pintype "bidirectional"))
    )
    (net (code "100") (name "unconnected-(U$3-PadNO)") (class "Default")
      (node (ref "U$3") (pin "NO") (pinfunction "NO_NO") (pintype "bidirectional"))
    )
    (net (code "101") (name "unconnected-(U3-CBUS2-Pad13)") (class "Default")
      (node (ref "U3") (pin "13") (pinfunction "CBUS2_13") (pintype "bidirectional"))
    )
    (net (code "102") (name "unconnected-(U3-CBUS3-Pad14)") (class "Default")
      (node (ref "U3") (pin "14") (pinfunction "CBUS3_14") (pintype "bidirectional"))
    )
    (net (code "103") (name "unconnected-(U3-CBUS4-Pad12)") (class "Default")
      (node (ref "U3") (pin "12") (pinfunction "CBUS4_12") (pintype "bidirectional"))
    )
    (net (code "104") (name "unconnected-(U3-CTS#-Pad11)") (class "Default")
      (node (ref "U3") (pin "11") (pinfunction "CTS#_11") (pintype "input"))
    )
    (net (code "105") (name "unconnected-(U3-DCD#-Pad10)") (class "Default")
      (node (ref "U3") (pin "10") (pinfunction "DCD#_10") (pintype "input"))
    )
    (net (code "106") (name "unconnected-(U3-DSR#-Pad9)") (class "Default")
      (node (ref "U3") (pin "9") (pinfunction "DSR#_9") (pintype "input"))
    )
    (net (code "107") (name "unconnected-(U3-DTR#-Pad2)") (class "Default")
      (node (ref "U3") (pin "2") (pinfunction "DTR#_2") (pintype "output"))
    )
    (net (code "108") (name "unconnected-(U3-OSCI-Pad27)") (class "Default")
      (node (ref "U3") (pin "27") (pinfunction "OSCI_27") (pintype "input"))
    )
    (net (code "109") (name "unconnected-(U3-OSCO-Pad28)") (class "Default")
      (node (ref "U3") (pin "28") (pinfunction "OSCO_28") (pintype "output"))
    )
    (net (code "110") (name "unconnected-(U3-RESET#-Pad19)") (class "Default")
      (node (ref "U3") (pin "19") (pinfunction "RESET#_19") (pintype "input"))
    )
    (net (code "111") (name "unconnected-(U3-RI#-Pad6)") (class "Default")
      (node (ref "U3") (pin "6") (pinfunction "RI#_6") (pintype "input"))
    )
    (net (code "112") (name "unconnected-(U3-RTS#-Pad3)") (class "Default")
      (node (ref "U3") (pin "3") (pinfunction "RTS#_3") (pintype "output"))
    )
  )
)
